# Wireless_Coordinator_v2_2.net
KiCad netlist of a schematic drawn in EAGLE
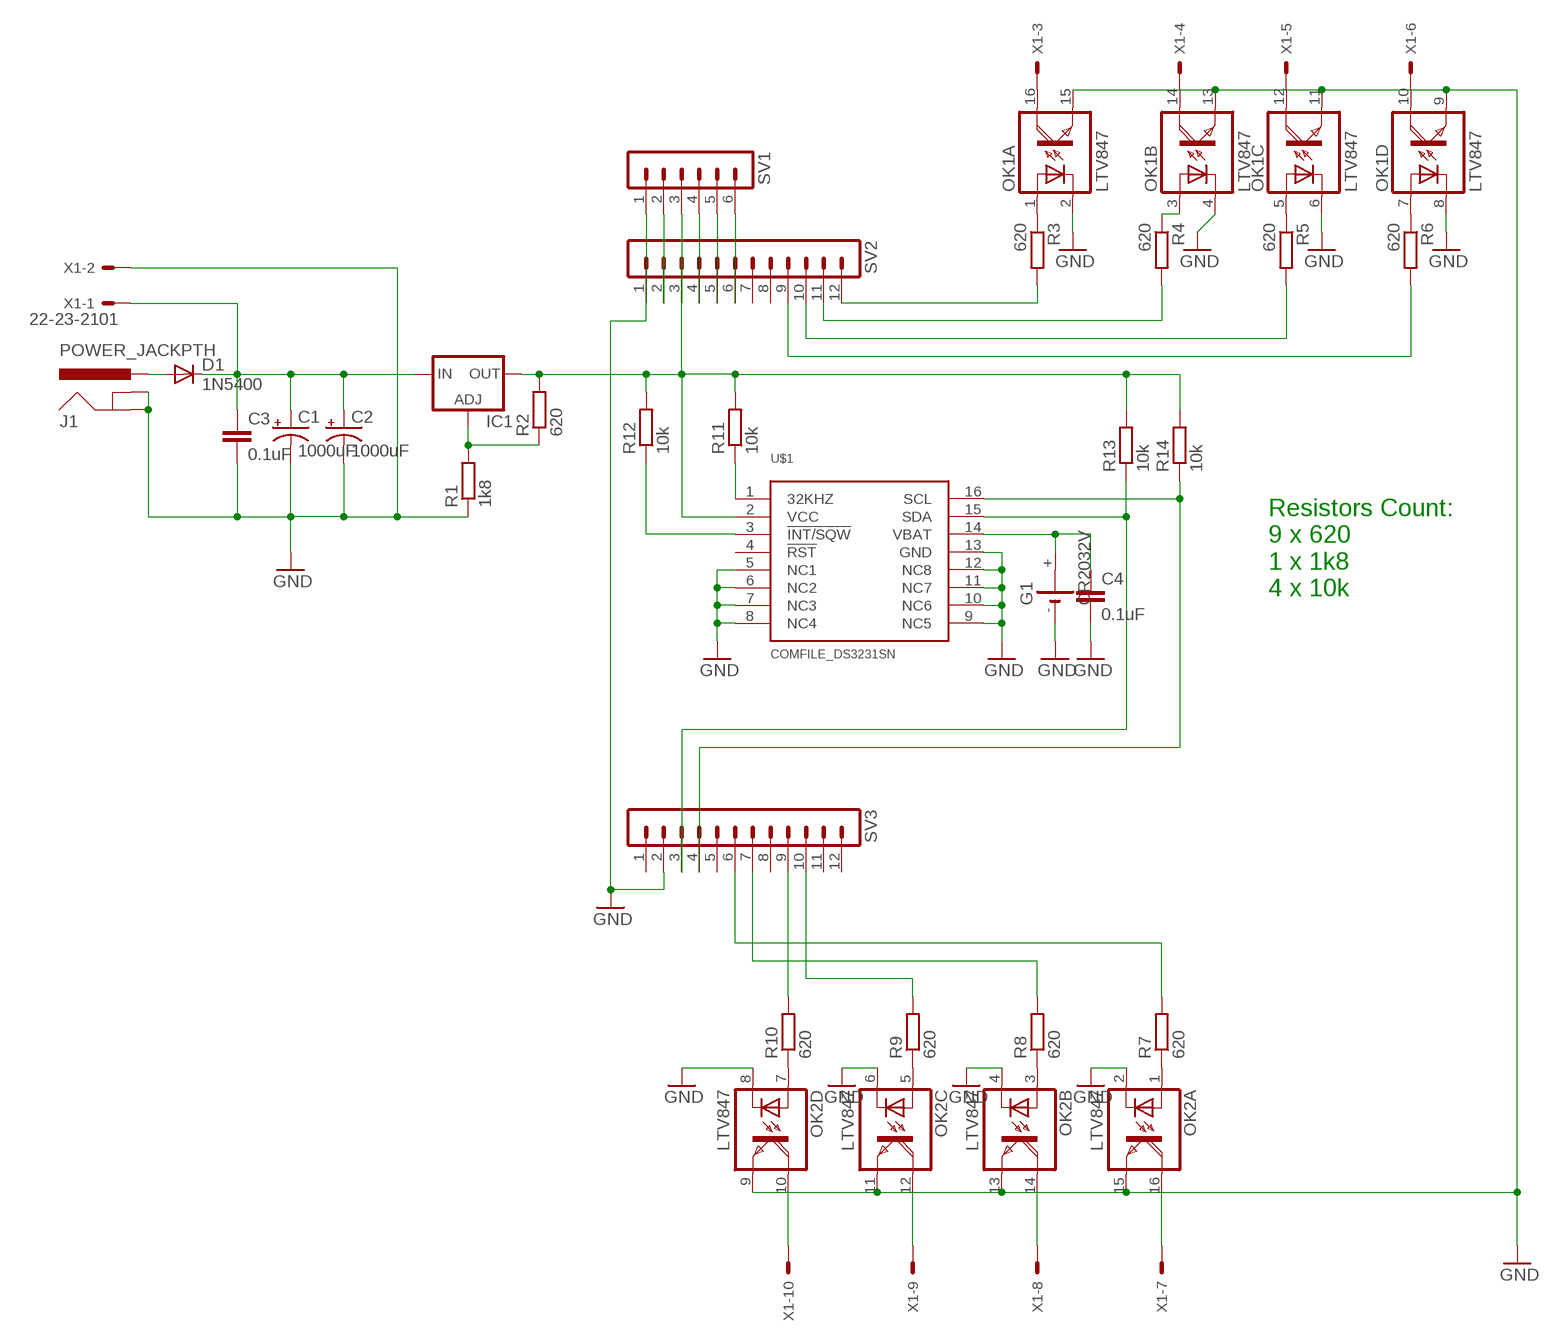
[diagram p0: schematic, sheet 1]

(export (version "E")
  (design (tool "Eeschema 10.0.6"))
  (components
    (comp (ref "C1")
      (value "1000uF")
      (footprint "eagle-import:E5-10,5")
      (libsource (lib "eagle-import") (part "CPOL-USE5-10.5"))
    )
    (comp (ref "C2")
      (value "1000uF")
      (footprint "eagle-import:E3,5-8")
      (libsource (lib "eagle-import") (part "CPOL-USE3.5-8"))
    )
    (comp (ref "C3")
      (value "0.1uF")
      (footprint "eagle-import:C050-025X075")
      (libsource (lib "eagle-import") (part "C-EU050-025X075"))
    )
    (comp (ref "C4")
      (value "0.1uF")
      (footprint "eagle-import:C050-025X075")
      (libsource (lib "eagle-import") (part "C-EU050-025X075"))
    )
    (comp (ref "D1")
      (value "1N5400")
      (footprint "eagle-import:DO201-15")
      (libsource (lib "eagle-import") (part "1N5400"))
    )
    (comp (ref "G1")
      (value "CR2032V")
      (footprint "eagle-import:CR2032V")
      (libsource (lib "eagle-import") (part "CR2032V"))
    )
    (comp (ref "IC1")
      (value "LM317TS")
      (footprint "eagle-import:317TS")
      (libsource (lib "eagle-import") (part "LM317TS"))
    )
    (comp (ref "J1")
      (value "POWER_JACKPTH")
      (footprint "eagle-import:POWER_JACK_PTH")
      (libsource (lib "eagle-import") (part "POWER_JACKPTH"))
    )
    (comp (ref "OK1")
      (value "LTV847")
      (footprint "eagle-import:DIL16")
      (fields (field (name "MF") "LITEON"))
      (libsource (lib "eagle-import") (part "LTV847"))
    )
    (comp (ref "OK2")
      (value "LTV847")
      (footprint "eagle-import:DIL16")
      (fields (field (name "MF") "LITEON"))
      (libsource (lib "eagle-import") (part "LTV847"))
    )
    (comp (ref "R1")
      (value "1k8")
      (footprint "eagle-import:0207_12")
      (libsource (lib "eagle-import") (part "R-EU_0207/12"))
    )
    (comp (ref "R2")
      (value "620")
      (footprint "eagle-import:0207_12")
      (libsource (lib "eagle-import") (part "R-EU_0207/12"))
    )
    (comp (ref "R3")
      (value "620")
      (footprint "eagle-import:0207_12")
      (libsource (lib "eagle-import") (part "R-EU_0207/12"))
    )
    (comp (ref "R4")
      (value "620")
      (footprint "eagle-import:0207_12")
      (libsource (lib "eagle-import") (part "R-EU_0207/12"))
    )
    (comp (ref "R5")
      (value "620")
      (footprint "eagle-import:0207_12")
      (libsource (lib "eagle-import") (part "R-EU_0207/12"))
    )
    (comp (ref "R6")
      (value "620")
      (footprint "eagle-import:0207_12")
      (libsource (lib "eagle-import") (part "R-EU_0207/12"))
    )
    (comp (ref "R7")
      (value "620")
      (footprint "eagle-import:0207_12")
      (libsource (lib "eagle-import") (part "R-EU_0207/12"))
    )
    (comp (ref "R8")
      (value "620")
      (footprint "eagle-import:0207_12")
      (libsource (lib "eagle-import") (part "R-EU_0207/12"))
    )
    (comp (ref "R9")
      (value "620")
      (footprint "eagle-import:0207_12")
      (libsource (lib "eagle-import") (part "R-EU_0207/12"))
    )
    (comp (ref "R10")
      (value "620")
      (footprint "eagle-import:0207_12")
      (libsource (lib "eagle-import") (part "R-EU_0207/12"))
    )
    (comp (ref "R11")
      (value "10k")
      (footprint "eagle-import:0207_12")
      (libsource (lib "eagle-import") (part "R-EU_0207/12"))
    )
    (comp (ref "R12")
      (value "10k")
      (footprint "eagle-import:0207_12")
      (libsource (lib "eagle-import") (part "R-EU_0207/12"))
    )
    (comp (ref "R13")
      (value "10k")
      (footprint "eagle-import:0207_12")
      (libsource (lib "eagle-import") (part "R-EU_0207/12"))
    )
    (comp (ref "R14")
      (value "10k")
      (footprint "eagle-import:0207_12")
      (libsource (lib "eagle-import") (part "R-EU_0207/12"))
    )
    (comp (ref "SV1")
      (value "MA06-1")
      (footprint "eagle-import:MA06-1")
      (libsource (lib "eagle-import") (part "MA06-1"))
    )
    (comp (ref "SV2")
      (value "MA12-1")
      (footprint "eagle-import:MA12-1")
      (libsource (lib "eagle-import") (part "MA12-1"))
    )
    (comp (ref "SV3")
      (value "MA12-1")
      (footprint "eagle-import:MA12-1")
      (libsource (lib "eagle-import") (part "MA12-1"))
    )
    (comp (ref "U$1")
      (value "COMFILE_DS3231SN")
      (footprint "eagle-import:COMFILE_SO16W")
      (libsource (lib "eagle-import") (part "COMFILE_DS3231SN"))
    )
    (comp (ref "X1")
      (value "22-23-2101")
      (footprint "eagle-import:22-23-2101")
      (fields (field (name "MF") "MOLEX"))
      (libsource (lib "eagle-import") (part "22-23-2101"))
    )
  )
  (nets
    (net (code "1") (name "GND") (class "Default")
      (node (ref "C1") (pin "-") (pinfunction "-_-") (pintype "passive"))
      (node (ref "C2") (pin "-") (pinfunction "-_-") (pintype "passive"))
      (node (ref "C3") (pin "2") (pinfunction "2_2") (pintype "passive"))
      (node (ref "C4") (pin "2") (pinfunction "2_2") (pintype "passive"))
      (node (ref "G1") (pin "-") (pinfunction "-_-") (pintype "passive"))
      (node (ref "J1") (pin "GND") (pinfunction "GND_GND") (pintype "bidirectional"))
      (node (ref "J1") (pin "GNDBREAK") (pinfunction "GNDBREAK_GNDBREAK") (pintype "bidirectional"))
      (node (ref "OK1") (pin "11") (pinfunction "EMI_11") (pintype "passive"))
      (node (ref "OK1") (pin "13") (pinfunction "EMI_13") (pintype "passive"))
      (node (ref "OK1") (pin "15") (pinfunction "EMI_15") (pintype "passive"))
      (node (ref "OK1") (pin "2") (pinfunction "C_2") (pintype "passive"))
      (node (ref "OK1") (pin "4") (pinfunction "C_4") (pintype "passive"))
      (node (ref "OK1") (pin "6") (pinfunction "C_6") (pintype "passive"))
      (node (ref "OK1") (pin "8") (pinfunction "C_8") (pintype "passive"))
      (node (ref "OK1") (pin "9") (pinfunction "EMI_9") (pintype "passive"))
      (node (ref "OK2") (pin "11") (pinfunction "EMI_11") (pintype "passive"))
      (node (ref "OK2") (pin "13") (pinfunction "EMI_13") (pintype "passive"))
      (node (ref "OK2") (pin "15") (pinfunction "EMI_15") (pintype "passive"))
      (node (ref "OK2") (pin "2") (pinfunction "C_2") (pintype "passive"))
      (node (ref "OK2") (pin "4") (pinfunction "C_4") (pintype "passive"))
      (node (ref "OK2") (pin "6") (pinfunction "C_6") (pintype "passive"))
      (node (ref "OK2") (pin "8") (pinfunction "C_8") (pintype "passive"))
      (node (ref "OK2") (pin "9") (pinfunction "EMI_9") (pintype "passive"))
      (node (ref "R1") (pin "1") (pinfunction "1_1") (pintype "passive"))
      (node (ref "SV1") (pin "1") (pinfunction "1_1") (pintype "passive"))
      (node (ref "SV2") (pin "1") (pinfunction "1_1") (pintype "passive"))
      (node (ref "SV3") (pin "2") (pinfunction "2_2") (pintype "passive"))
      (node (ref "U$1") (pin "10") (pinfunction "NC6_10") (pintype "bidirectional"))
      (node (ref "U$1") (pin "11") (pinfunction "NC7_11") (pintype "bidirectional"))
      (node (ref "U$1") (pin "12") (pinfunction "NC8_12") (pintype "bidirectional"))
      (node (ref "U$1") (pin "13") (pinfunction "GND_13") (pintype "bidirectional"))
      (node (ref "U$1") (pin "5") (pinfunction "NC1_5") (pintype "bidirectional"))
      (node (ref "U$1") (pin "6") (pinfunction "NC2_6") (pintype "bidirectional"))
      (node (ref "U$1") (pin "7") (pinfunction "NC3_7") (pintype "bidirectional"))
      (node (ref "U$1") (pin "8") (pinfunction "NC4_8") (pintype "bidirectional"))
      (node (ref "U$1") (pin "9") (pinfunction "NC5_9") (pintype "bidirectional"))
      (node (ref "X1") (pin "2") (pinfunction "S_2") (pintype "passive"))
    )
    (net (code "2") (name "Net-(D1-PadA)") (class "Default")
      (node (ref "D1") (pin "A") (pinfunction "A_A") (pintype "passive"))
      (node (ref "J1") (pin "PWR") (pinfunction "PWR_PWR") (pintype "bidirectional"))
    )
    (net (code "3") (name "Net-(IC1-ADJ)") (class "Default")
      (node (ref "IC1") (pin "1") (pinfunction "ADJ_1") (pintype "input"))
      (node (ref "R1") (pin "2") (pinfunction "2_2") (pintype "passive"))
      (node (ref "R2") (pin "1") (pinfunction "1_1") (pintype "passive"))
    )
    (net (code "4") (name "Net-(IC1-IN)") (class "Default")
      (node (ref "C1") (pin "+") (pinfunction "+_+") (pintype "passive"))
      (node (ref "C2") (pin "+") (pinfunction "+_+") (pintype "passive"))
      (node (ref "C3") (pin "1") (pinfunction "1_1") (pintype "passive"))
      (node (ref "D1") (pin "C") (pinfunction "C_C") (pintype "passive"))
      (node (ref "IC1") (pin "3") (pinfunction "IN_3") (pintype "input"))
      (node (ref "X1") (pin "1") (pinfunction "S_1") (pintype "passive"))
    )
    (net (code "5") (name "Net-(IC1-OUT)") (class "Default")
      (node (ref "IC1") (pin "2") (pinfunction "OUT_2") (pintype "passive"))
      (node (ref "R11") (pin "2") (pinfunction "2_2") (pintype "passive"))
      (node (ref "R12") (pin "2") (pinfunction "2_2") (pintype "passive"))
      (node (ref "R13") (pin "2") (pinfunction "2_2") (pintype "passive"))
      (node (ref "R14") (pin "2") (pinfunction "2_2") (pintype "passive"))
      (node (ref "R2") (pin "2") (pinfunction "2_2") (pintype "passive"))
      (node (ref "SV1") (pin "3") (pinfunction "3_3") (pintype "passive"))
      (node (ref "SV2") (pin "3") (pinfunction "3_3") (pintype "passive"))
      (node (ref "U$1") (pin "2") (pinfunction "VCC_2") (pintype "bidirectional"))
    )
    (net (code "6") (name "Net-(OK1A-A)") (class "Default")
      (node (ref "OK1") (pin "1") (pinfunction "A_1") (pintype "passive"))
      (node (ref "R3") (pin "1") (pinfunction "1_1") (pintype "passive"))
    )
    (net (code "7") (name "Net-(OK1A-COL)") (class "Default")
      (node (ref "OK1") (pin "16") (pinfunction "COL_16") (pintype "passive"))
      (node (ref "X1") (pin "3") (pinfunction "S_3") (pintype "passive"))
    )
    (net (code "8") (name "Net-(OK1B-A)") (class "Default")
      (node (ref "OK1") (pin "3") (pinfunction "A_3") (pintype "passive"))
      (node (ref "R4") (pin "1") (pinfunction "1_1") (pintype "passive"))
    )
    (net (code "9") (name "Net-(OK1B-COL)") (class "Default")
      (node (ref "OK1") (pin "14") (pinfunction "COL_14") (pintype "passive"))
      (node (ref "X1") (pin "4") (pinfunction "S_4") (pintype "passive"))
    )
    (net (code "10") (name "Net-(OK1C-A)") (class "Default")
      (node (ref "OK1") (pin "5") (pinfunction "A_5") (pintype "passive"))
      (node (ref "R5") (pin "1") (pinfunction "1_1") (pintype "passive"))
    )
    (net (code "11") (name "Net-(OK1C-COL)") (class "Default")
      (node (ref "OK1") (pin "12") (pinfunction "COL_12") (pintype "passive"))
      (node (ref "X1") (pin "5") (pinfunction "S_5") (pintype "passive"))
    )
    (net (code "12") (name "Net-(OK1D-A)") (class "Default")
      (node (ref "OK1") (pin "7") (pinfunction "A_7") (pintype "passive"))
      (node (ref "R6") (pin "1") (pinfunction "1_1") (pintype "passive"))
    )
    (net (code "13") (name "Net-(OK1D-COL)") (class "Default")
      (node (ref "OK1") (pin "10") (pinfunction "COL_10") (pintype "passive"))
      (node (ref "X1") (pin "6") (pinfunction "S_6") (pintype "passive"))
    )
    (net (code "14") (name "Net-(OK2A-A)") (class "Default")
      (node (ref "OK2") (pin "1") (pinfunction "A_1") (pintype "passive"))
      (node (ref "R7") (pin "1") (pinfunction "1_1") (pintype "passive"))
    )
    (net (code "15") (name "Net-(OK2A-COL)") (class "Default")
      (node (ref "OK2") (pin "16") (pinfunction "COL_16") (pintype "passive"))
      (node (ref "X1") (pin "7") (pinfunction "S_7") (pintype "passive"))
    )
    (net (code "16") (name "Net-(OK2B-A)") (class "Default")
      (node (ref "OK2") (pin "3") (pinfunction "A_3") (pintype "passive"))
      (node (ref "R8") (pin "1") (pinfunction "1_1") (pintype "passive"))
    )
    (net (code "17") (name "Net-(OK2B-COL)") (class "Default")
      (node (ref "OK2") (pin "14") (pinfunction "COL_14") (pintype "passive"))
      (node (ref "X1") (pin "8") (pinfunction "S_8") (pintype "passive"))
    )
    (net (code "18") (name "Net-(OK2C-A)") (class "Default")
      (node (ref "OK2") (pin "5") (pinfunction "A_5") (pintype "passive"))
      (node (ref "R9") (pin "1") (pinfunction "1_1") (pintype "passive"))
    )
    (net (code "19") (name "Net-(OK2C-COL)") (class "Default")
      (node (ref "OK2") (pin "12") (pinfunction "COL_12") (pintype "passive"))
      (node (ref "X1") (pin "9") (pinfunction "S_9") (pintype "passive"))
    )
    (net (code "20") (name "Net-(OK2D-A)") (class "Default")
      (node (ref "OK2") (pin "7") (pinfunction "A_7") (pintype "passive"))
      (node (ref "R10") (pin "1") (pinfunction "1_1") (pintype "passive"))
    )
    (net (code "21") (name "Net-(OK2D-COL)") (class "Default")
      (node (ref "OK2") (pin "10") (pinfunction "COL_10") (pintype "passive"))
      (node (ref "X1") (pin "10") (pinfunction "S_10") (pintype "passive"))
    )
    (net (code "22") (name "Net-(R3-Pad2)") (class "Default")
      (node (ref "R3") (pin "2") (pinfunction "2_2") (pintype "passive"))
      (node (ref "SV2") (pin "12") (pinfunction "12_12") (pintype "passive"))
    )
    (net (code "23") (name "Net-(R4-Pad2)") (class "Default")
      (node (ref "R4") (pin "2") (pinfunction "2_2") (pintype "passive"))
      (node (ref "SV2") (pin "11") (pinfunction "11_11") (pintype "passive"))
    )
    (net (code "24") (name "Net-(R5-Pad2)") (class "Default")
      (node (ref "R5") (pin "2") (pinfunction "2_2") (pintype "passive"))
      (node (ref "SV2") (pin "10") (pinfunction "10_10") (pintype "passive"))
    )
    (net (code "25") (name "Net-(R6-Pad2)") (class "Default")
      (node (ref "R6") (pin "2") (pinfunction "2_2") (pintype "passive"))
      (node (ref "SV2") (pin "9") (pinfunction "9_9") (pintype "passive"))
    )
    (net (code "26") (name "Net-(R7-Pad2)") (class "Default")
      (node (ref "R7") (pin "2") (pinfunction "2_2") (pintype "passive"))
      (node (ref "SV3") (pin "6") (pinfunction "6_6") (pintype "passive"))
    )
    (net (code "27") (name "Net-(R8-Pad2)") (class "Default")
      (node (ref "R8") (pin "2") (pinfunction "2_2") (pintype "passive"))
      (node (ref "SV3") (pin "7") (pinfunction "7_7") (pintype "passive"))
    )
    (net (code "28") (name "Net-(R9-Pad2)") (class "Default")
      (node (ref "R9") (pin "2") (pinfunction "2_2") (pintype "passive"))
      (node (ref "SV3") (pin "10") (pinfunction "10_10") (pintype "passive"))
    )
    (net (code "29") (name "Net-(R10-Pad2)") (class "Default")
      (node (ref "R10") (pin "2") (pinfunction "2_2") (pintype "passive"))
      (node (ref "SV3") (pin "9") (pinfunction "9_9") (pintype "passive"))
    )
    (net (code "30") (name "Net-(SV1-Pad2)") (class "Default")
      (node (ref "SV1") (pin "2") (pinfunction "2_2") (pintype "passive"))
      (node (ref "SV2") (pin "2") (pinfunction "2_2") (pintype "passive"))
    )
    (net (code "31") (name "Net-(SV1-Pad4)") (class "Default")
      (node (ref "SV1") (pin "4") (pinfunction "4_4") (pintype "passive"))
      (node (ref "SV2") (pin "4") (pinfunction "4_4") (pintype "passive"))
    )
    (net (code "32") (name "Net-(SV1-Pad5)") (class "Default")
      (node (ref "SV1") (pin "5") (pinfunction "5_5") (pintype "passive"))
      (node (ref "SV2") (pin "5") (pinfunction "5_5") (pintype "passive"))
    )
    (net (code "33") (name "Net-(SV1-Pad6)") (class "Default")
      (node (ref "SV1") (pin "6") (pinfunction "6_6") (pintype "passive"))
      (node (ref "SV2") (pin "6") (pinfunction "6_6") (pintype "passive"))
    )
    (net (code "34") (name "Net-(U$1-32KHZ)") (class "Default")
      (node (ref "R11") (pin "1") (pinfunction "1_1") (pintype "passive"))
      (node (ref "U$1") (pin "1") (pinfunction "32KHZ_1") (pintype "bidirectional"))
    )
    (net (code "35") (name "Net-(U$1-SCL)") (class "Default")
      (node (ref "R14") (pin "1") (pinfunction "1_1") (pintype "passive"))
      (node (ref "SV3") (pin "4") (pinfunction "4_4") (pintype "passive"))
      (node (ref "U$1") (pin "16") (pinfunction "SCL_16") (pintype "bidirectional"))
    )
    (net (code "36") (name "Net-(U$1-SDA)") (class "Default")
      (node (ref "R13") (pin "1") (pinfunction "1_1") (pintype "passive"))
      (node (ref "SV3") (pin "3") (pinfunction "3_3") (pintype "passive"))
      (node (ref "U$1") (pin "15") (pinfunction "SDA_15") (pintype "bidirectional"))
    )
    (net (code "37") (name "Net-(U$1-VBAT)") (class "Default")
      (node (ref "C4") (pin "1") (pinfunction "1_1") (pintype "passive"))
      (node (ref "G1") (pin "+") (pinfunction "+_+") (pintype "passive"))
      (node (ref "U$1") (pin "14") (pinfunction "VBAT_14") (pintype "bidirectional"))
    )
    (net (code "38") (name "Net-(U$1-~{INT{slash}SQW})") (class "Default")
      (node (ref "R12") (pin "1") (pinfunction "1_1") (pintype "passive"))
      (node (ref "U$1") (pin "3") (pinfunction "~{INT/SQW}_3") (pintype "bidirectional"))
    )
    (net (code "39") (name "unconnected-(G1-+-Pad+@1)") (class "Default")
      (node (ref "G1") (pin "+@1") (pinfunction "+_+@1") (pintype "passive"))
    )
    (net (code "40") (name "unconnected-(SV2-Pad7)") (class "Default")
      (node (ref "SV2") (pin "7") (pinfunction "7_7") (pintype "passive"))
    )
    (net (code "41") (name "unconnected-(SV2-Pad8)") (class "Default")
      (node (ref "SV2") (pin "8") (pinfunction "8_8") (pintype "passive"))
    )
    (net (code "42") (name "unconnected-(SV3-Pad1)") (class "Default")
      (node (ref "SV3") (pin "1") (pinfunction "1_1") (pintype "passive"))
    )
    (net (code "43") (name "unconnected-(SV3-Pad5)") (class "Default")
      (node (ref "SV3") (pin "5") (pinfunction "5_5") (pintype "passive"))
    )
    (net (code "44") (name "unconnected-(SV3-Pad8)") (class "Default")
      (node (ref "SV3") (pin "8") (pinfunction "8_8") (pintype "passive"))
    )
    (net (code "45") (name "unconnected-(SV3-Pad11)") (class "Default")
      (node (ref "SV3") (pin "11") (pinfunction "11_11") (pintype "passive"))
    )
    (net (code "46") (name "unconnected-(SV3-Pad12)") (class "Default")
      (node (ref "SV3") (pin "12") (pinfunction "12_12") (pintype "passive"))
    )
    (net (code "47") (name "unconnected-(U$1-~{RST}-Pad4)") (class "Default")
      (node (ref "U$1") (pin "4") (pinfunction "~{RST}_4") (pintype "bidirectional"))
    )
  )
)
